# Gate_Control.net
KiCad netlist of a schematic drawn in Altium Designer
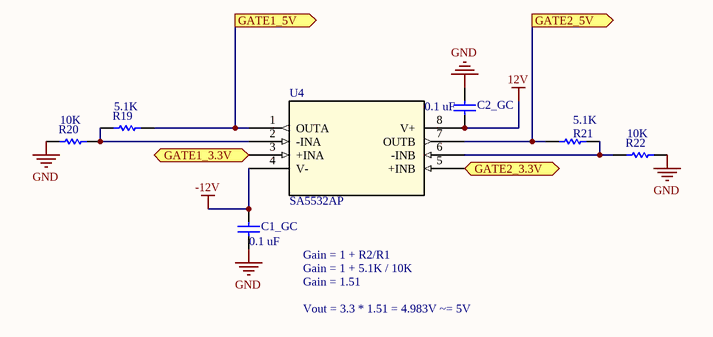
[diagram p0: Gate_Control.SchDoc]

(export (version "E")
  (design (tool "Eeschema 10.0.6"))
  (components
    (comp (ref "C1_GC")
      (value "0.1 uF")
      (footprint "C0805")
      (description "Capacitor")
      (fields (field (name "PUBLISHER") "Altium Limited"))
      (libsource (lib "Miscellaneous Devices") (part "Cap"))
    )
    (comp (ref "C2_GC")
      (value "0.1 uF")
      (footprint "C0805")
      (description "Capacitor")
      (fields (field (name "PUBLISHER") "Altium Limited"))
      (libsource (lib "Miscellaneous Devices") (part "Cap"))
    )
    (comp (ref "R19")
      (value "5.1K")
      (footprint "AXIAL-0.3")
      (description "Resistor")
      (fields (field (name "Comment") "Res1") (field (name "PUBLISHER") "Altium Limited"))
      (libsource (lib "Miscellaneous Devices") (part "Res1"))
    )
    (comp (ref "R20")
      (value "10K")
      (footprint "AXIAL-0.3")
      (description "Resistor")
      (fields (field (name "Comment") "Res1") (field (name "PUBLISHER") "Altium Limited"))
      (libsource (lib "Miscellaneous Devices") (part "Res1"))
    )
    (comp (ref "R21")
      (value "5.1K")
      (footprint "AXIAL-0.3")
      (description "Resistor")
      (fields (field (name "Comment") "Res1") (field (name "PUBLISHER") "Altium Limited"))
      (libsource (lib "Miscellaneous Devices") (part "Res1"))
    )
    (comp (ref "R22")
      (value "10K")
      (footprint "AXIAL-0.3")
      (description "Resistor")
      (fields (field (name "Comment") "Res1") (field (name "PUBLISHER") "Altium Limited"))
      (libsource (lib "Miscellaneous Devices") (part "Res1"))
    )
    (comp (ref "U4")
      (value "SA5532AP")
      (footprint "PDIP-8_N")
      (description "Imported")
      (fields
        (field (name "MANUFACTURER_PART_NUMBER") "LT1632CN8#PBF")
        (field (name "DIGIKEYPARTNUMBER") "LT1632CN8-ND")
        (field (name "COPYRIGHT") "Copyright (C) 2015 Accelerated Designs. All rights reserved")
      )
      (libsource (lib "lt1632") (part "LT1632CN8#PBF"))
    )
  )
  (nets
    (net (code "1") (name "-12V") (class "Default")
      (node (ref "C1_GC") (pin "2") (pinfunction "2_2") (pintype "passive"))
      (node (ref "U4") (pin "4") (pinfunction "V-_4") (pintype "power_in"))
    )
    (net (code "2") (name "/GATE1_3.3V") (class "Default")
      (node (ref "U4") (pin "3") (pinfunction "+INA_3") (pintype "input"))
    )
    (net (code "3") (name "/GATE1_5V") (class "Default")
      (node (ref "R19") (pin "2") (pinfunction "2_2") (pintype "passive"))
      (node (ref "U4") (pin "1") (pinfunction "OUTA_1") (pintype "output"))
    )
    (net (code "4") (name "/GATE2_3.3V") (class "Default")
      (node (ref "U4") (pin "5") (pinfunction "+INB_5") (pintype "input"))
    )
    (net (code "5") (name "/GATE2_5V") (class "Default")
      (node (ref "R21") (pin "1") (pinfunction "1_1") (pintype "passive"))
      (node (ref "U4") (pin "7") (pinfunction "OUTB_7") (pintype "output"))
    )
    (net (code "6") (name "12V") (class "Default")
      (node (ref "C2_GC") (pin "1") (pinfunction "1_1") (pintype "passive"))
      (node (ref "U4") (pin "8") (pinfunction "V+_8") (pintype "power_in"))
    )
    (net (code "7") (name "GND") (class "Default")
      (node (ref "C1_GC") (pin "1") (pinfunction "1_1") (pintype "passive"))
      (node (ref "C2_GC") (pin "2") (pinfunction "2_2") (pintype "passive"))
      (node (ref "R20") (pin "1") (pinfunction "1_1") (pintype "passive"))
      (node (ref "R22") (pin "2") (pinfunction "2_2") (pintype "passive"))
    )
    (net (code "8") (name "Net-(U4--INA)") (class "Default")
      (node (ref "R19") (pin "1") (pinfunction "1_1") (pintype "passive"))
      (node (ref "R20") (pin "2") (pinfunction "2_2") (pintype "passive"))
      (node (ref "U4") (pin "2") (pinfunction "-INA_2") (pintype "input"))
    )
    (net (code "9") (name "Net-(U4--INB)") (class "Default")
      (node (ref "R21") (pin "2") (pinfunction "2_2") (pintype "passive"))
      (node (ref "R22") (pin "1") (pinfunction "1_1") (pintype "passive"))
      (node (ref "U4") (pin "6") (pinfunction "-INB_6") (pintype "input"))
    )
  )
)
